# channel.net
KiCad netlist of a schematic drawn in Altium Designer
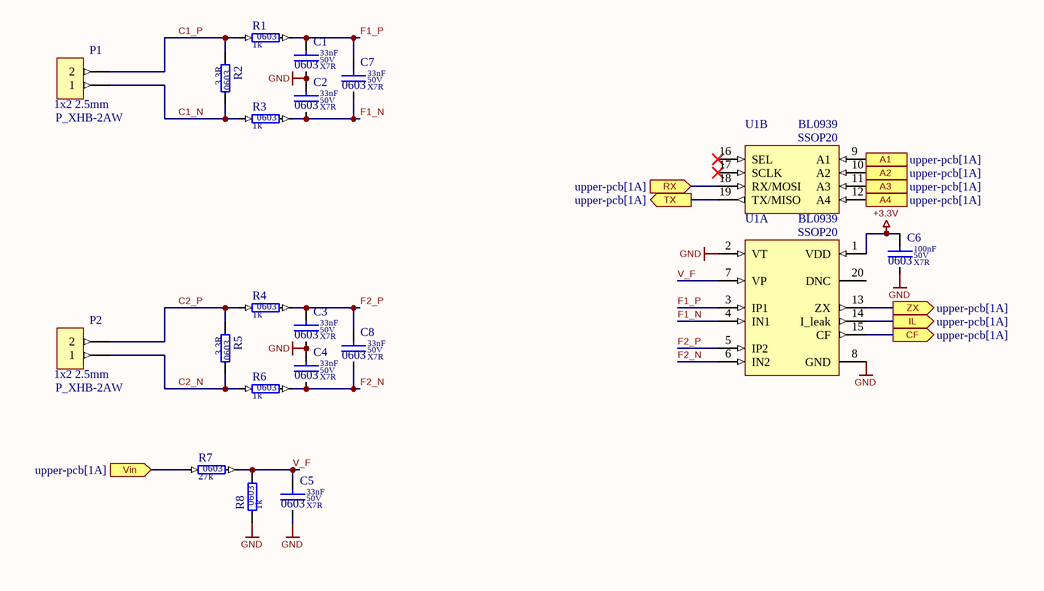
[diagram p0: channel.SchDoc]

(export (version "E")
  (design (tool "Eeschema 10.0.6"))
  (components
    (comp (ref "C1")
      (value "33nF")
      (footprint "C_0603_1608")
      (description "Capacitor")
      (fields
        (field (name "DIELECTRIC") "X7R")
        (field (name "VOLTAGE") "50V")
        (field (name "SCH_FOOTPRINT") "0603")
        (field (name "PART NUMBER") "C_33nF_50V_X7R_0603_10")
        (field (name "MANUFACTURER") "Yageo")
      )
      (libsource (lib "Library") (part "C"))
    )
    (comp (ref "C2")
      (value "33nF")
      (footprint "C_0603_1608")
      (description "Capacitor")
      (fields
        (field (name "DIELECTRIC") "X7R")
        (field (name "VOLTAGE") "50V")
        (field (name "SCH_FOOTPRINT") "0603")
        (field (name "PART NUMBER") "C_33nF_50V_X7R_0603_10")
        (field (name "MANUFACTURER") "Yageo")
      )
      (libsource (lib "Library") (part "C"))
    )
    (comp (ref "C3")
      (value "33nF")
      (footprint "C_0603_1608")
      (description "Capacitor")
      (fields
        (field (name "DIELECTRIC") "X7R")
        (field (name "VOLTAGE") "50V")
        (field (name "SCH_FOOTPRINT") "0603")
        (field (name "PART NUMBER") "C_33nF_50V_X7R_0603_10")
        (field (name "MANUFACTURER") "Yageo")
      )
      (libsource (lib "Library") (part "C"))
    )
    (comp (ref "C4")
      (value "33nF")
      (footprint "C_0603_1608")
      (description "Capacitor")
      (fields
        (field (name "DIELECTRIC") "X7R")
        (field (name "VOLTAGE") "50V")
        (field (name "SCH_FOOTPRINT") "0603")
        (field (name "PART NUMBER") "C_33nF_50V_X7R_0603_10")
        (field (name "MANUFACTURER") "Yageo")
      )
      (libsource (lib "Library") (part "C"))
    )
    (comp (ref "C5")
      (value "33nF")
      (footprint "C_0603_1608")
      (description "Capacitor")
      (fields
        (field (name "DIELECTRIC") "X7R")
        (field (name "VOLTAGE") "50V")
        (field (name "SCH_FOOTPRINT") "0603")
        (field (name "PART NUMBER") "C_33nF_50V_X7R_0603_10")
        (field (name "MANUFACTURER") "Yageo")
      )
      (libsource (lib "Library") (part "C"))
    )
    (comp (ref "C6")
      (value "100nF")
      (footprint "C_0603_1608")
      (description "Capacitor")
      (fields
        (field (name "DIELECTRIC") "X7R")
        (field (name "VOLTAGE") "50V")
        (field (name "SCH_FOOTPRINT") "0603")
        (field (name "PART NUMBER") "C_100nF_50V_X7R_0603_5")
        (field (name "MANUFACTURER") "Samsung")
      )
      (libsource (lib "Library") (part "C"))
    )
    (comp (ref "C7")
      (value "33nF")
      (footprint "C_0603_1608")
      (description "Capacitor")
      (fields
        (field (name "DIELECTRIC") "X7R")
        (field (name "VOLTAGE") "50V")
        (field (name "SCH_FOOTPRINT") "0603")
        (field (name "PART NUMBER") "C_33nF_50V_X7R_0603_10")
        (field (name "MANUFACTURER") "Yageo")
      )
      (libsource (lib "Library") (part "C"))
    )
    (comp (ref "C8")
      (value "33nF")
      (footprint "C_0603_1608")
      (description "Capacitor")
      (fields
        (field (name "DIELECTRIC") "X7R")
        (field (name "VOLTAGE") "50V")
        (field (name "SCH_FOOTPRINT") "0603")
        (field (name "PART NUMBER") "C_33nF_50V_X7R_0603_10")
        (field (name "MANUFACTURER") "Yageo")
      )
      (libsource (lib "Library") (part "C"))
    )
    (comp (ref "P1")
      (value "P_XHB-2AW")
      (footprint "P_XHB-2AW")
      (description "Pin Header")
      (fields (field (name "SCH_FOOTPRINT") "1x2 2.5mm") (field (name "Comment") "XHB"))
      (libsource (lib "Library") (part "P_HEADER_1x2"))
    )
    (comp (ref "P2")
      (value "P_XHB-2AW")
      (footprint "P_XHB-2AW")
      (description "Pin Header")
      (fields (field (name "SCH_FOOTPRINT") "1x2 2.5mm") (field (name "Comment") "XHB"))
      (libsource (lib "Library") (part "P_HEADER_1x2"))
    )
    (comp (ref "R1")
      (value "1k")
      (footprint "R_0603_1608")
      (fields
        (field (name "SCH_FOOTPRINT") "0603")
        (field (name "PART NUMBER") "R_1k_0603_1")
        (field (name "VOLTAGE") "75V")
        (field (name "POWER") "100mW")
      )
      (libsource (lib "Library") (part "R"))
    )
    (comp (ref "R2")
      (value "3.3R")
      (footprint "R_0603_1608")
      (fields
        (field (name "SCH_FOOTPRINT") "0603")
        (field (name "PART NUMBER") "R_3.3R_0603_5")
        (field (name "VOLTAGE") "50V")
        (field (name "POWER") "100mW")
      )
      (libsource (lib "") (part "R_1"))
    )
    (comp (ref "R3")
      (value "1k")
      (footprint "R_0603_1608")
      (fields
        (field (name "SCH_FOOTPRINT") "0603")
        (field (name "PART NUMBER") "R_1k_0603_1")
        (field (name "VOLTAGE") "75V")
        (field (name "POWER") "100mW")
      )
      (libsource (lib "Library") (part "R"))
    )
    (comp (ref "R4")
      (value "1k")
      (footprint "R_0603_1608")
      (fields
        (field (name "SCH_FOOTPRINT") "0603")
        (field (name "PART NUMBER") "R_1k_0603_1")
        (field (name "VOLTAGE") "75V")
        (field (name "POWER") "100mW")
      )
      (libsource (lib "Library") (part "R"))
    )
    (comp (ref "R5")
      (value "3.3R")
      (footprint "R_0603_1608")
      (fields
        (field (name "SCH_FOOTPRINT") "0603")
        (field (name "PART NUMBER") "R_3.3R_0603_5")
        (field (name "VOLTAGE") "50V")
        (field (name "POWER") "100mW")
      )
      (libsource (lib "") (part "R_1"))
    )
    (comp (ref "R6")
      (value "1k")
      (footprint "R_0603_1608")
      (fields
        (field (name "SCH_FOOTPRINT") "0603")
        (field (name "PART NUMBER") "R_1k_0603_1")
        (field (name "VOLTAGE") "75V")
        (field (name "POWER") "100mW")
      )
      (libsource (lib "Library") (part "R"))
    )
    (comp (ref "R7")
      (value "27k")
      (footprint "R_0603_1608")
      (fields
        (field (name "SCH_FOOTPRINT") "0603")
        (field (name "PART NUMBER") "R_27k_0603_1")
        (field (name "VOLTAGE") "75V")
        (field (name "POWER") "100mW")
      )
      (libsource (lib "Library") (part "R"))
    )
    (comp (ref "R8")
      (value "1k")
      (footprint "R_0603_1608")
      (fields
        (field (name "SCH_FOOTPRINT") "0603")
        (field (name "PART NUMBER") "R_1k_0603_1")
        (field (name "VOLTAGE") "75V")
        (field (name "POWER") "100mW")
      )
      (libsource (lib "") (part "R_1"))
    )
    (comp (ref "U1")
      (value "BL0939")
      (footprint "SSOP20_3.9x8.65")
      (fields
        (field (name "SCH_FOOTPRINT") "SSOP20")
        (field (name "PART NUMBER") "U_BL0939")
        (field (name "MANUFACTURER") "Belling")
        (field (name "Comment") "Electrical mains 2-ch power meter")
      )
      (libsource (lib "Library") (part "U_BL0939"))
    )
  )
  (nets
    (net (code "1") (name "+3.3V") (class "Default")
      (node (ref "C6") (pin "1") (pinfunction "1_1") (pintype "passive"))
      (node (ref "U1") (pin "1") (pinfunction "VDD_1") (pintype "input"))
    )
    (net (code "2") (name "/A1") (class "Default")
      (node (ref "U1") (pin "9") (pinfunction "A1_9") (pintype "input"))
    )
    (net (code "3") (name "/A2") (class "Default")
      (node (ref "U1") (pin "10") (pinfunction "A2_10") (pintype "input"))
    )
    (net (code "4") (name "/A3") (class "Default")
      (node (ref "U1") (pin "11") (pinfunction "A3_11") (pintype "input"))
    )
    (net (code "5") (name "/A4") (class "Default")
      (node (ref "U1") (pin "12") (pinfunction "A4_12") (pintype "input"))
    )
    (net (code "6") (name "/C1_N") (class "Default")
      (node (ref "P1") (pin "1") (pinfunction "1_1") (pintype "output"))
      (node (ref "R2") (pin "2") (pinfunction "2_2") (pintype "passive"))
      (node (ref "R3") (pin "1") (pinfunction "1_1") (pintype "input"))
    )
    (net (code "7") (name "/C1_P") (class "Default")
      (node (ref "P1") (pin "2") (pinfunction "2_2") (pintype "output"))
      (node (ref "R1") (pin "1") (pinfunction "1_1") (pintype "input"))
      (node (ref "R2") (pin "1") (pinfunction "1_1") (pintype "passive"))
    )
    (net (code "8") (name "/C2_N") (class "Default")
      (node (ref "P2") (pin "1") (pinfunction "1_1") (pintype "output"))
      (node (ref "R5") (pin "2") (pinfunction "2_2") (pintype "passive"))
      (node (ref "R6") (pin "1") (pinfunction "1_1") (pintype "input"))
    )
    (net (code "9") (name "/C2_P") (class "Default")
      (node (ref "P2") (pin "2") (pinfunction "2_2") (pintype "output"))
      (node (ref "R4") (pin "1") (pinfunction "1_1") (pintype "input"))
      (node (ref "R5") (pin "1") (pinfunction "1_1") (pintype "passive"))
    )
    (net (code "10") (name "/CF") (class "Default")
      (node (ref "U1") (pin "15") (pinfunction "CF_15") (pintype "output"))
    )
    (net (code "11") (name "/F1_N") (class "Default")
      (node (ref "C2") (pin "2") (pinfunction "2_2") (pintype "passive"))
      (node (ref "C7") (pin "2") (pinfunction "2_2") (pintype "passive"))
      (node (ref "R3") (pin "2") (pinfunction "2_2") (pintype "output"))
      (node (ref "U1") (pin "4") (pinfunction "IN1_4") (pintype "input"))
    )
    (net (code "12") (name "/F1_P") (class "Default")
      (node (ref "C1") (pin "1") (pinfunction "1_1") (pintype "passive"))
      (node (ref "C7") (pin "1") (pinfunction "1_1") (pintype "passive"))
      (node (ref "R1") (pin "2") (pinfunction "2_2") (pintype "output"))
      (node (ref "U1") (pin "3") (pinfunction "IP1_3") (pintype "input"))
    )
    (net (code "13") (name "/F2_N") (class "Default")
      (node (ref "C4") (pin "2") (pinfunction "2_2") (pintype "passive"))
      (node (ref "C8") (pin "2") (pinfunction "2_2") (pintype "passive"))
      (node (ref "R6") (pin "2") (pinfunction "2_2") (pintype "output"))
      (node (ref "U1") (pin "6") (pinfunction "IN2_6") (pintype "input"))
    )
    (net (code "14") (name "/F2_P") (class "Default")
      (node (ref "C3") (pin "1") (pinfunction "1_1") (pintype "passive"))
      (node (ref "C8") (pin "1") (pinfunction "1_1") (pintype "passive"))
      (node (ref "R4") (pin "2") (pinfunction "2_2") (pintype "output"))
      (node (ref "U1") (pin "5") (pinfunction "IP2_5") (pintype "input"))
    )
    (net (code "15") (name "/IL") (class "Default")
      (node (ref "U1") (pin "14") (pinfunction "I_leak_14") (pintype "output"))
    )
    (net (code "16") (name "/RX") (class "Default")
      (node (ref "U1") (pin "18") (pinfunction "RX/MOSI_18") (pintype "input"))
    )
    (net (code "17") (name "/TX") (class "Default")
      (node (ref "U1") (pin "19") (pinfunction "TX/MISO_19") (pintype "output"))
    )
    (net (code "18") (name "/V_F") (class "Default")
      (node (ref "C5") (pin "1") (pinfunction "1_1") (pintype "passive"))
      (node (ref "R7") (pin "2") (pinfunction "2_2") (pintype "output"))
      (node (ref "R8") (pin "2") (pinfunction "2_2") (pintype "passive"))
      (node (ref "U1") (pin "7") (pinfunction "VP_7") (pintype "input"))
    )
    (net (code "19") (name "/Vin") (class "Default")
      (node (ref "R7") (pin "1") (pinfunction "1_1") (pintype "input"))
    )
    (net (code "20") (name "/ZX") (class "Default")
      (node (ref "U1") (pin "13") (pinfunction "ZX_13") (pintype "output"))
    )
    (net (code "21") (name "GND") (class "Default")
      (node (ref "C1") (pin "2") (pinfunction "2_2") (pintype "passive"))
      (node (ref "C2") (pin "1") (pinfunction "1_1") (pintype "passive"))
      (node (ref "C3") (pin "2") (pinfunction "2_2") (pintype "passive"))
      (node (ref "C4") (pin "1") (pinfunction "1_1") (pintype "passive"))
      (node (ref "C5") (pin "2") (pinfunction "2_2") (pintype "passive"))
      (node (ref "C6") (pin "2") (pinfunction "2_2") (pintype "passive"))
      (node (ref "R8") (pin "1") (pinfunction "1_1") (pintype "passive"))
      (node (ref "U1") (pin "2") (pinfunction "VT_2") (pintype "input"))
      (node (ref "U1") (pin "8") (pinfunction "GND_8") (pintype "power_in"))
    )
    (net (code "22") (name "unconnected-(U1A-DNC-Pad20)") (class "Default")
      (node (ref "U1") (pin "20") (pinfunction "DNC_20") (pintype "passive"))
    )
    (net (code "23") (name "unconnected-(U1B-SCLK-Pad17)") (class "Default")
      (node (ref "U1") (pin "17") (pinfunction "SCLK_17") (pintype "input+no_connect"))
    )
    (net (code "24") (name "unconnected-(U1B-SEL-Pad16)") (class "Default")
      (node (ref "U1") (pin "16") (pinfunction "SEL_16") (pintype "input+no_connect"))
    )
  )
)
